# ESP8266_MODULE_HEADER.net
KiCad netlist of a schematic drawn in EAGLE
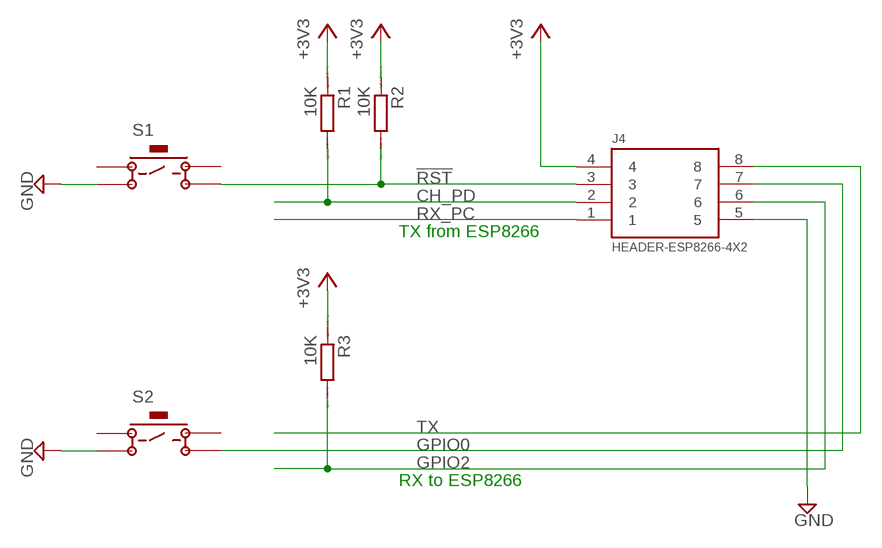
[diagram p0: schematic, sheet 1]

(export (version "E")
  (design (tool "Eeschema 10.0.6"))
  (components
    (comp (ref "J4")
      (value "HEADER-ESP8266-4X2")
      (footprint "eagle-import:HEADER-4X2-A")
      (libsource (lib "eagle-import") (part "HEADER-ESP8266-4X2"))
    )
    (comp (ref "R1")
      (value "10K")
      (footprint "eagle-import:0204_7")
      (libsource (lib "eagle-import") (part "R-EU_0204_7"))
    )
    (comp (ref "R2")
      (value "10K")
      (footprint "eagle-import:0204_7")
      (libsource (lib "eagle-import") (part "R-EU_0204_7"))
    )
    (comp (ref "R3")
      (value "10K")
      (footprint "eagle-import:0204_7")
      (libsource (lib "eagle-import") (part "R-EU_0204_7"))
    )
    (comp (ref "S1")
      (value "1825910-6-SPST-NOPB-4P")
      (footprint "eagle-import:SW-NOPB-4")
      (libsource (lib "eagle-import") (part "1825910-6-SPST-NOPB-4P"))
    )
    (comp (ref "S2")
      (value "1825910-6-SPST-NOPB-4P")
      (footprint "eagle-import:SW-NOPB-4")
      (libsource (lib "eagle-import") (part "1825910-6-SPST-NOPB-4P"))
    )
  )
  (nets
    (net (code "1") (name "+3V3") (class "Default")
      (node (ref "J4") (pin "4") (pinfunction "4_4") (pintype "bidirectional"))
      (node (ref "R1") (pin "1") (pinfunction "1_1") (pintype "passive"))
      (node (ref "R2") (pin "1") (pinfunction "1_1") (pintype "passive"))
      (node (ref "R3") (pin "1") (pinfunction "1_1") (pintype "passive"))
    )
    (net (code "2") (name "/CH_PD") (class "Default")
      (node (ref "J4") (pin "2") (pinfunction "2_2") (pintype "bidirectional"))
      (node (ref "R1") (pin "2") (pinfunction "2_2") (pintype "passive"))
    )
    (net (code "3") (name "/GPIO0") (class "Default")
      (node (ref "J4") (pin "7") (pinfunction "7_7") (pintype "bidirectional"))
      (node (ref "S2") (pin "4") (pinfunction "4_4") (pintype "bidirectional"))
    )
    (net (code "4") (name "/GPIO2") (class "Default")
      (node (ref "J4") (pin "6") (pinfunction "6_6") (pintype "bidirectional"))
      (node (ref "R3") (pin "2") (pinfunction "2_2") (pintype "passive"))
    )
    (net (code "5") (name "/RX_PC") (class "Default")
      (node (ref "J4") (pin "1") (pinfunction "1_1") (pintype "bidirectional"))
    )
    (net (code "6") (name "/TX") (class "Default")
      (node (ref "J4") (pin "8") (pinfunction "8_8") (pintype "bidirectional"))
    )
    (net (code "7") (name "/~{RST}") (class "Default")
      (node (ref "J4") (pin "3") (pinfunction "3_3") (pintype "bidirectional"))
      (node (ref "R2") (pin "2") (pinfunction "2_2") (pintype "passive"))
      (node (ref "S1") (pin "4") (pinfunction "4_4") (pintype "bidirectional"))
    )
    (net (code "8") (name "GND") (class "Default")
      (node (ref "J4") (pin "5") (pinfunction "5_5") (pintype "bidirectional"))
      (node (ref "S1") (pin "2") (pinfunction "2_2") (pintype "bidirectional"))
      (node (ref "S2") (pin "2") (pinfunction "2_2") (pintype "bidirectional"))
    )
    (net (code "9") (name "unconnected-(S1-Pad1)") (class "Default")
      (node (ref "S1") (pin "1") (pinfunction "1_1") (pintype "bidirectional"))
    )
    (net (code "10") (name "unconnected-(S1-Pad3)") (class "Default")
      (node (ref "S1") (pin "3") (pinfunction "3_3") (pintype "bidirectional"))
    )
    (net (code "11") (name "unconnected-(S2-Pad1)") (class "Default")
      (node (ref "S2") (pin "1") (pinfunction "1_1") (pintype "bidirectional"))
    )
    (net (code "12") (name "unconnected-(S2-Pad3)") (class "Default")
      (node (ref "S2") (pin "3") (pinfunction "3_3") (pintype "bidirectional"))
    )
  )
)
